# SUSTAINIAC_BO.net
KiCad netlist of a schematic drawn in Altium Designer
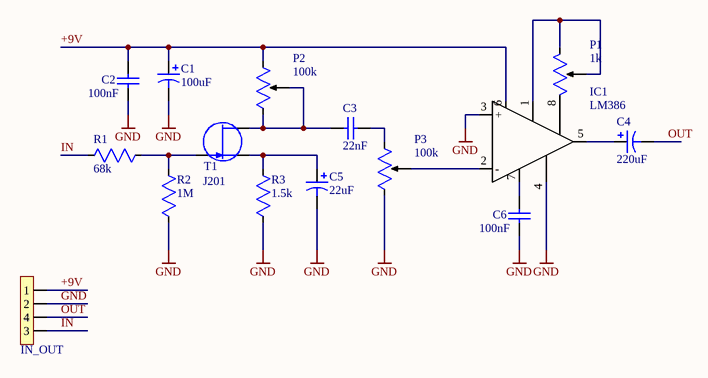
[diagram p0: SUSTAINIAC_BO.SchDoc]

(export (version "E")
  (design (tool "Eeschema 10.0.6"))
  (components
    (comp (ref "C1")
      (value "100uF")
      (footprint "PANASONIC_C_BO")
      (fields (field (name "Comment") "Capacitor_Pol"))
      (libsource (lib "BartoszOstrowski") (part "Capacitor_Pol"))
    )
    (comp (ref "C2")
      (value "100nF")
      (footprint "SMD_1206_BO")
      (fields (field (name "Comment") "Capacitor"))
      (libsource (lib "BartoszOstrowski") (part "Capacitor"))
    )
    (comp (ref "C3")
      (value "22nF")
      (footprint "SMD_1206_BO")
      (fields (field (name "Comment") "Capacitor"))
      (libsource (lib "BartoszOstrowski") (part "Capacitor"))
    )
    (comp (ref "C4")
      (value "220uF")
      (footprint "PANASONIC_D8_BO")
      (fields (field (name "Comment") "Capacitor_Pol"))
      (libsource (lib "BartoszOstrowski") (part "Capacitor_Pol"))
    )
    (comp (ref "C5")
      (value "22uF")
      (footprint "PANASONIC_B_BO")
      (fields (field (name "Comment") "Capacitor_Pol"))
      (libsource (lib "BartoszOstrowski") (part "Capacitor_Pol"))
    )
    (comp (ref "C6")
      (value "100nF")
      (footprint "SMD_1206_BO")
      (fields (field (name "Comment") "Capacitor"))
      (libsource (lib "BartoszOstrowski") (part "Capacitor"))
    )
    (comp (ref "Con1")
      (value "IN_OUT")
      (footprint "Connector double")
      (libsource (lib "BartoszOstrowski") (part "CONNECTOR_4_PIN"))
    )
    (comp (ref "IC1")
      (value "LM386")
      (footprint "SO8_BO")
      (libsource (lib "BartoszOstrowski") (part "LM386"))
    )
    (comp (ref "P1")
      (value "Potentiometer")
      (footprint "POT_1801-J_BO")
      (fields (field (name "RESISTANCE") "1k"))
      (libsource (lib "BartoszOstrowski") (part "Potentiometer"))
    )
    (comp (ref "P2")
      (value "Potentiometer")
      (footprint "POT_1801-J_BO")
      (fields (field (name "RESISTANCE") "100k"))
      (libsource (lib "BartoszOstrowski") (part "Potentiometer"))
    )
    (comp (ref "P3")
      (value "Potentiometer")
      (footprint "POT_1801-J_BO")
      (fields (field (name "RESISTANCE") "100k"))
      (libsource (lib "BartoszOstrowski") (part "Potentiometer"))
    )
    (comp (ref "R1")
      (value "Resistor")
      (footprint "SMD_1206_BO")
      (fields (field (name "RESISTANCE") "68k"))
      (libsource (lib "BartoszOstrowski") (part "Resistor"))
    )
    (comp (ref "R2")
      (value "Resistor")
      (footprint "SMD_1206_BO")
      (fields (field (name "RESISTANCE") "1M"))
      (libsource (lib "BartoszOstrowski") (part "Resistor"))
    )
    (comp (ref "R3")
      (value "Resistor")
      (footprint "SMD_1206_BO")
      (fields (field (name "RESISTANCE") "1.5k"))
      (libsource (lib "BartoszOstrowski") (part "Resistor"))
    )
    (comp (ref "T1") (value "J201") (footprint "SOT23_BO") (libsource (lib "BartoszOstrowski") (part "JFET")))
  )
  (nets
    (net (code "1") (name "/+9V") (class "Default")
      (node (ref "C1") (pin "1") (pinfunction "1_1") (pintype "passive"))
      (node (ref "C2") (pin "2") (pinfunction "2_2") (pintype "passive"))
      (node (ref "Con1") (pin "1") (pinfunction "1_1") (pintype "passive"))
      (node (ref "IC1") (pin "6") (pinfunction "6_6") (pintype "passive"))
      (node (ref "P2") (pin "3") (pinfunction "3_3") (pintype "passive"))
    )
    (net (code "2") (name "/IN") (class "Default")
      (node (ref "Con1") (pin "3") (pinfunction "3_3") (pintype "passive"))
      (node (ref "R1") (pin "1") (pinfunction "OUT_1") (pintype "passive"))
    )
    (net (code "3") (name "/OUT") (class "Default")
      (node (ref "C4") (pin "2") (pinfunction "2_2") (pintype "passive"))
      (node (ref "Con1") (pin "4") (pinfunction "4_4") (pintype "passive"))
    )
    (net (code "4") (name "GND") (class "Default")
      (node (ref "C1") (pin "2") (pinfunction "2_2") (pintype "passive"))
      (node (ref "C2") (pin "1") (pinfunction "1_1") (pintype "passive"))
      (node (ref "C5") (pin "2") (pinfunction "2_2") (pintype "passive"))
      (node (ref "C6") (pin "1") (pinfunction "1_1") (pintype "passive"))
      (node (ref "Con1") (pin "2") (pinfunction "2_2") (pintype "passive"))
      (node (ref "IC1") (pin "3") (pinfunction "+_3") (pintype "passive"))
      (node (ref "IC1") (pin "4") (pinfunction "4_4") (pintype "passive"))
      (node (ref "P3") (pin "1") (pinfunction "1_1") (pintype "passive"))
      (node (ref "R2") (pin "1") (pinfunction "OUT_1") (pintype "passive"))
      (node (ref "R3") (pin "1") (pinfunction "OUT_1") (pintype "passive"))
    )
    (net (code "5") (name "Net-(C3-Pad2)") (class "Default")
      (node (ref "C3") (pin "2") (pinfunction "2_2") (pintype "passive"))
      (node (ref "P3") (pin "3") (pinfunction "3_3") (pintype "passive"))
    )
    (net (code "6") (name "Net-(C4-Pad1)") (class "Default")
      (node (ref "C4") (pin "1") (pinfunction "1_1") (pintype "passive"))
      (node (ref "IC1") (pin "5") (pinfunction "5_5") (pintype "passive"))
    )
    (net (code "7") (name "Net-(C6-Pad2)") (class "Default")
      (node (ref "C6") (pin "2") (pinfunction "2_2") (pintype "passive"))
      (node (ref "IC1") (pin "7") (pinfunction "7_7") (pintype "passive"))
    )
    (net (code "8") (name "Net-(IC1--)") (class "Default")
      (node (ref "IC1") (pin "2") (pinfunction "-_2") (pintype "passive"))
      (node (ref "P3") (pin "2") (pinfunction "2_2") (pintype "passive"))
    )
    (net (code "9") (name "Net-(IC1-Pad1)") (class "Default")
      (node (ref "IC1") (pin "1") (pinfunction "1_1") (pintype "passive"))
      (node (ref "P1") (pin "1") (pinfunction "1_1") (pintype "passive"))
      (node (ref "P1") (pin "2") (pinfunction "2_2") (pintype "passive"))
    )
    (net (code "10") (name "Net-(IC1-Pad8)") (class "Default")
      (node (ref "IC1") (pin "8") (pinfunction "8_8") (pintype "passive"))
      (node (ref "P1") (pin "3") (pinfunction "3_3") (pintype "passive"))
    )
    (net (code "11") (name "Net-(T1-D)") (class "Default")
      (node (ref "C5") (pin "1") (pinfunction "1_1") (pintype "passive"))
      (node (ref "R3") (pin "2") (pinfunction "OUT_2") (pintype "passive"))
      (node (ref "T1") (pin "1") (pinfunction "D_1") (pintype "passive"))
    )
    (net (code "12") (name "Net-(T1-G)") (class "Default")
      (node (ref "R1") (pin "2") (pinfunction "OUT_2") (pintype "passive"))
      (node (ref "R2") (pin "2") (pinfunction "OUT_2") (pintype "passive"))
      (node (ref "T1") (pin "3") (pinfunction "G_3") (pintype "passive"))
    )
    (net (code "13") (name "Net-(T1-S)") (class "Default")
      (node (ref "C3") (pin "1") (pinfunction "1_1") (pintype "passive"))
      (node (ref "P2") (pin "1") (pinfunction "1_1") (pintype "passive"))
      (node (ref "P2") (pin "2") (pinfunction "2_2") (pintype "passive"))
      (node (ref "T1") (pin "2") (pinfunction "S_2") (pintype "passive"))
    )
  )
)
